# Temp_sensors_Input.net
KiCad netlist of a schematic drawn in Altium Designer
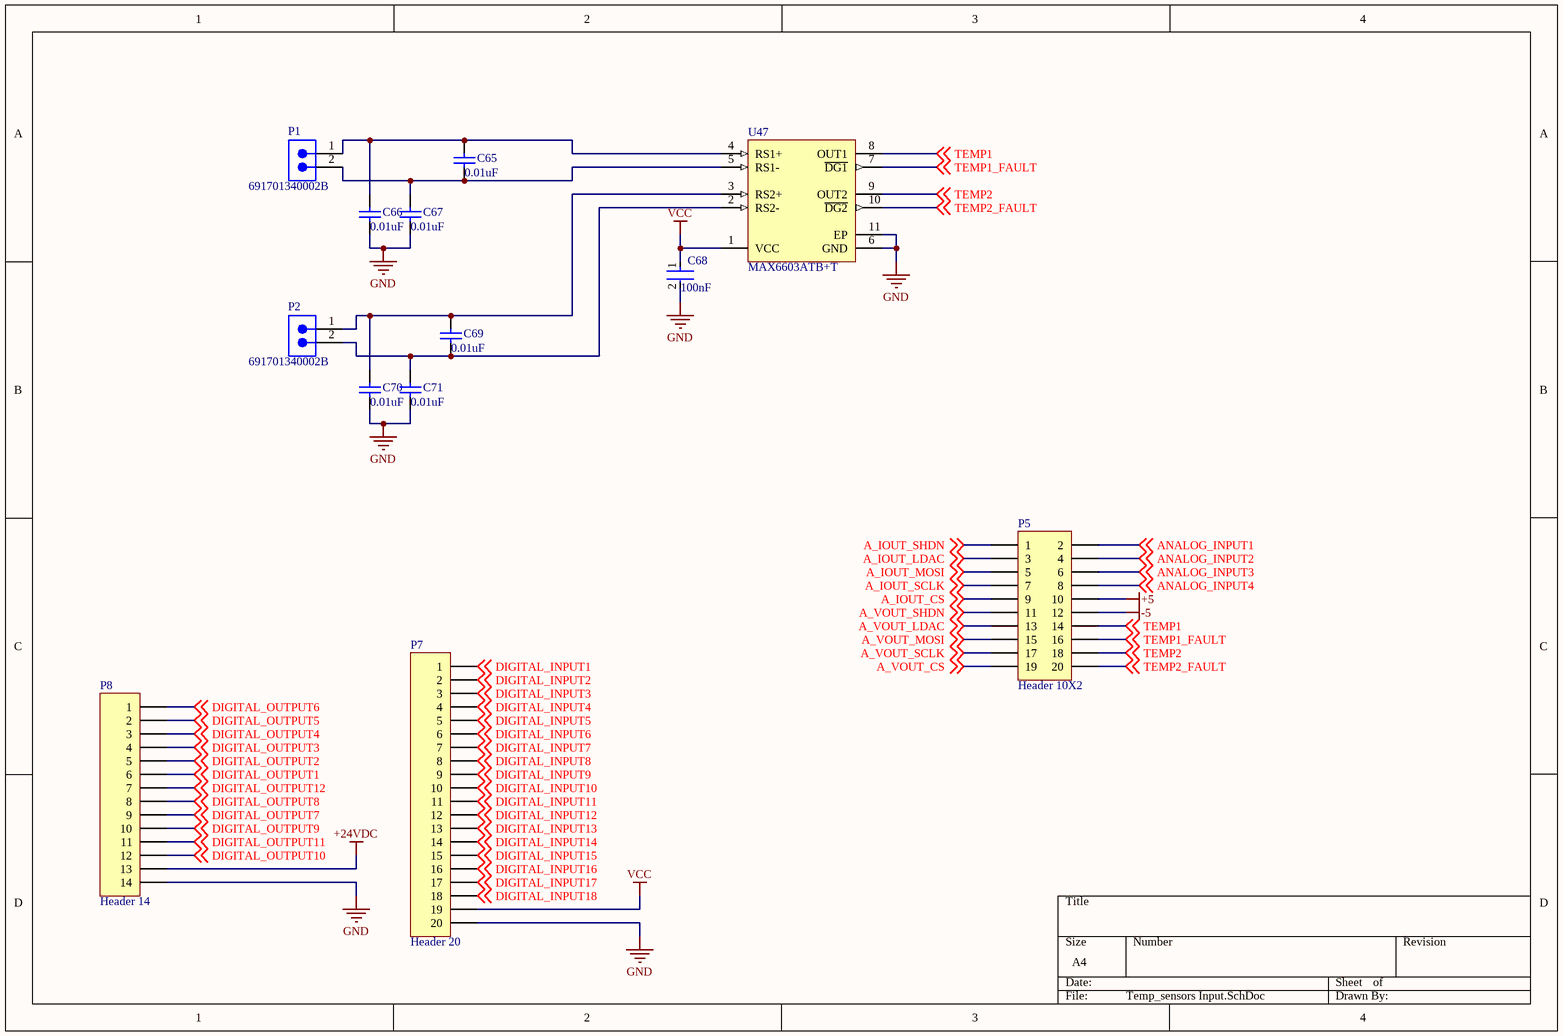
[diagram p0: Temp_sensors Input.SchDoc]

(export (version "E")
  (design (tool "Eeschema 10.0.6"))
  (components
    (comp (ref "C65")
      (value "0.01uF")
      (footprint "CAPC1608X92X38ML15T08")
      (fields (field (name "MANUFACTURER") "Vitramon") (field (name "PART NUMBER") "VJ0603Y103KXAAP"))
      (libsource (lib "Altium Content Vault") (part "CAP"))
    )
    (comp (ref "C66")
      (value "0.01uF")
      (footprint "CAPC1608X92X38ML15T08")
      (fields (field (name "MANUFACTURER") "Vitramon") (field (name "PART NUMBER") "VJ0603Y103KXAAP"))
      (libsource (lib "Altium Content Vault") (part "CAP"))
    )
    (comp (ref "C67")
      (value "0.01uF")
      (footprint "CAPC1608X92X38ML15T08")
      (fields (field (name "MANUFACTURER") "Vitramon") (field (name "PART NUMBER") "VJ0603Y103KXAAP"))
      (libsource (lib "Altium Content Vault") (part "CAP"))
    )
    (comp (ref "C68")
      (value "08051C104K4T2A")
      (footprint "FP-0805-L_2_01_0_2-W_1_25-IPC_B")
      (description "Automotive Ceramic Capacitor, 0805, 100nF, 10%, X7R, 15%, 100V")
      (fields
        (field (name "TOLERANCE") "10%")
        (field (name "CAPACITANCE") "100nF")
        (field (name "VOLTAGE") "100V")
      )
      (libsource (lib "Altium Content Vault") (part "b4654b650e69147ec39a6b967a45e02"))
    )
    (comp (ref "C69")
      (value "0.01uF")
      (footprint "CAPC1608X92X38ML15T08")
      (fields (field (name "MANUFACTURER") "Vitramon") (field (name "PART NUMBER") "VJ0603Y103KXAAP"))
      (libsource (lib "Altium Content Vault") (part "CAP"))
    )
    (comp (ref "C70")
      (value "0.01uF")
      (footprint "CAPC1608X92X38ML15T08")
      (fields (field (name "MANUFACTURER") "Vitramon") (field (name "PART NUMBER") "VJ0603Y103KXAAP"))
      (libsource (lib "Altium Content Vault") (part "CAP"))
    )
    (comp (ref "C71")
      (value "0.01uF")
      (footprint "CAPC1608X92X38ML15T08")
      (fields (field (name "MANUFACTURER") "Vitramon") (field (name "PART NUMBER") "VJ0603Y103KXAAP"))
      (libsource (lib "Altium Content Vault") (part "CAP"))
    )
    (comp (ref "P1")
      (value "691701340002B")
      (footprint "691701340002B")
      (libsource (lib "Altium Content Vault") (part "TBL - 1R - 02P - Male"))
    )
    (comp (ref "P2")
      (value "691701340002B")
      (footprint "691701340002B")
      (libsource (lib "Altium Content Vault") (part "TBL - 1R - 02P - Male"))
    )
    (comp (ref "P5")
      (value "Header 10X2")
      (footprint "HDR2X10")
      (description "Header, 10-Pin, Dual row")
      (fields (field (name "PUBLISHER") "Altium Limited"))
      (libsource (lib "Miscellaneous Connectors") (part "Header 10X2"))
    )
    (comp (ref "P7")
      (value "Header 20")
      (footprint "HDR1X20")
      (description "Header, 20-Pin")
      (fields (field (name "PUBLISHER") "Altium Limited"))
      (libsource (lib "Miscellaneous Connectors") (part "Header 20"))
    )
    (comp (ref "P8")
      (value "Header 14")
      (footprint "HDR1X14")
      (description "Header, 14-Pin")
      (fields (field (name "PUBLISHER") "Altium Limited"))
      (libsource (lib "Miscellaneous Connectors") (part "Header 14"))
    )
    (comp (ref "U47")
      (value "MAX6603ATB+T")
      (footprint "MAXM-T1033+1_V")
      (fields (field (name "GENERIC PART NUMBER") "MAX6603"))
      (libsource (lib "Altium Content Vault") (part "MAX6603-T1033"))
    )
  )
  (nets
    (net (code "1") (name "+5") (class "Default")
      (node (ref "P5") (pin "10") (pinfunction "10_10") (pintype "passive"))
    )
    (net (code "2") (name "+24VDC") (class "Default")
      (node (ref "P8") (pin "13") (pinfunction "13_13") (pintype "passive"))
    )
    (net (code "3") (name "-5") (class "Default")
      (node (ref "P5") (pin "12") (pinfunction "12_12") (pintype "passive"))
    )
    (net (code "4") (name "ANALOG_INPUT1") (class "Default")
      (node (ref "P5") (pin "2") (pinfunction "2_2") (pintype "passive"))
    )
    (net (code "5") (name "ANALOG_INPUT2") (class "Default")
      (node (ref "P5") (pin "4") (pinfunction "4_4") (pintype "passive"))
    )
    (net (code "6") (name "ANALOG_INPUT3") (class "Default")
      (node (ref "P5") (pin "6") (pinfunction "6_6") (pintype "passive"))
    )
    (net (code "7") (name "ANALOG_INPUT4") (class "Default")
      (node (ref "P5") (pin "8") (pinfunction "8_8") (pintype "passive"))
    )
    (net (code "8") (name "A_IOUT_CS") (class "Default")
      (node (ref "P5") (pin "9") (pinfunction "9_9") (pintype "passive"))
    )
    (net (code "9") (name "A_IOUT_LDAC") (class "Default")
      (node (ref "P5") (pin "3") (pinfunction "3_3") (pintype "passive"))
    )
    (net (code "10") (name "A_IOUT_MOSI") (class "Default")
      (node (ref "P5") (pin "5") (pinfunction "5_5") (pintype "passive"))
    )
    (net (code "11") (name "A_IOUT_SCLK") (class "Default")
      (node (ref "P5") (pin "7") (pinfunction "7_7") (pintype "passive"))
    )
    (net (code "12") (name "A_IOUT_SHDN") (class "Default")
      (node (ref "P5") (pin "1") (pinfunction "1_1") (pintype "passive"))
    )
    (net (code "13") (name "A_VOUT_CS") (class "Default")
      (node (ref "P5") (pin "19") (pinfunction "19_19") (pintype "passive"))
    )
    (net (code "14") (name "A_VOUT_LDAC") (class "Default")
      (node (ref "P5") (pin "13") (pinfunction "13_13") (pintype "passive"))
    )
    (net (code "15") (name "A_VOUT_MOSI") (class "Default")
      (node (ref "P5") (pin "15") (pinfunction "15_15") (pintype "passive"))
    )
    (net (code "16") (name "A_VOUT_SCLK") (class "Default")
      (node (ref "P5") (pin "17") (pinfunction "17_17") (pintype "passive"))
    )
    (net (code "17") (name "A_VOUT_SHDN") (class "Default")
      (node (ref "P5") (pin "11") (pinfunction "11_11") (pintype "passive"))
    )
    (net (code "18") (name "DIGITAL_INPUT1") (class "Default")
      (node (ref "P7") (pin "1") (pinfunction "1_1") (pintype "passive"))
    )
    (net (code "19") (name "DIGITAL_INPUT2") (class "Default")
      (node (ref "P7") (pin "2") (pinfunction "2_2") (pintype "passive"))
    )
    (net (code "20") (name "DIGITAL_INPUT3") (class "Default")
      (node (ref "P7") (pin "3") (pinfunction "3_3") (pintype "passive"))
    )
    (net (code "21") (name "DIGITAL_INPUT4") (class "Default")
      (node (ref "P7") (pin "4") (pinfunction "4_4") (pintype "passive"))
    )
    (net (code "22") (name "DIGITAL_INPUT5") (class "Default")
      (node (ref "P7") (pin "5") (pinfunction "5_5") (pintype "passive"))
    )
    (net (code "23") (name "DIGITAL_INPUT6") (class "Default")
      (node (ref "P7") (pin "6") (pinfunction "6_6") (pintype "passive"))
    )
    (net (code "24") (name "DIGITAL_INPUT7") (class "Default")
      (node (ref "P7") (pin "7") (pinfunction "7_7") (pintype "passive"))
    )
    (net (code "25") (name "DIGITAL_INPUT8") (class "Default")
      (node (ref "P7") (pin "8") (pinfunction "8_8") (pintype "passive"))
    )
    (net (code "26") (name "DIGITAL_INPUT9") (class "Default")
      (node (ref "P7") (pin "9") (pinfunction "9_9") (pintype "passive"))
    )
    (net (code "27") (name "DIGITAL_INPUT10") (class "Default")
      (node (ref "P7") (pin "10") (pinfunction "10_10") (pintype "passive"))
    )
    (net (code "28") (name "DIGITAL_INPUT11") (class "Default")
      (node (ref "P7") (pin "11") (pinfunction "11_11") (pintype "passive"))
    )
    (net (code "29") (name "DIGITAL_INPUT12") (class "Default")
      (node (ref "P7") (pin "12") (pinfunction "12_12") (pintype "passive"))
    )
    (net (code "30") (name "DIGITAL_INPUT13") (class "Default")
      (node (ref "P7") (pin "13") (pinfunction "13_13") (pintype "passive"))
    )
    (net (code "31") (name "DIGITAL_INPUT14") (class "Default")
      (node (ref "P7") (pin "14") (pinfunction "14_14") (pintype "passive"))
    )
    (net (code "32") (name "DIGITAL_INPUT15") (class "Default")
      (node (ref "P7") (pin "15") (pinfunction "15_15") (pintype "passive"))
    )
    (net (code "33") (name "DIGITAL_INPUT16") (class "Default")
      (node (ref "P7") (pin "16") (pinfunction "16_16") (pintype "passive"))
    )
    (net (code "34") (name "DIGITAL_INPUT17") (class "Default")
      (node (ref "P7") (pin "17") (pinfunction "17_17") (pintype "passive"))
    )
    (net (code "35") (name "DIGITAL_INPUT18") (class "Default")
      (node (ref "P7") (pin "18") (pinfunction "18_18") (pintype "passive"))
    )
    (net (code "36") (name "DIGITAL_OUTPUT1") (class "Default")
      (node (ref "P8") (pin "6") (pinfunction "6_6") (pintype "passive"))
    )
    (net (code "37") (name "DIGITAL_OUTPUT2") (class "Default")
      (node (ref "P8") (pin "5") (pinfunction "5_5") (pintype "passive"))
    )
    (net (code "38") (name "DIGITAL_OUTPUT3") (class "Default")
      (node (ref "P8") (pin "4") (pinfunction "4_4") (pintype "passive"))
    )
    (net (code "39") (name "DIGITAL_OUTPUT4") (class "Default")
      (node (ref "P8") (pin "3") (pinfunction "3_3") (pintype "passive"))
    )
    (net (code "40") (name "DIGITAL_OUTPUT5") (class "Default")
      (node (ref "P8") (pin "2") (pinfunction "2_2") (pintype "passive"))
    )
    (net (code "41") (name "DIGITAL_OUTPUT6") (class "Default")
      (node (ref "P8") (pin "1") (pinfunction "1_1") (pintype "passive"))
    )
    (net (code "42") (name "DIGITAL_OUTPUT7") (class "Default")
      (node (ref "P8") (pin "9") (pinfunction "9_9") (pintype "passive"))
    )
    (net (code "43") (name "DIGITAL_OUTPUT8") (class "Default")
      (node (ref "P8") (pin "8") (pinfunction "8_8") (pintype "passive"))
    )
    (net (code "44") (name "DIGITAL_OUTPUT9") (class "Default")
      (node (ref "P8") (pin "10") (pinfunction "10_10") (pintype "passive"))
    )
    (net (code "45") (name "DIGITAL_OUTPUT10") (class "Default")
      (node (ref "P8") (pin "12") (pinfunction "12_12") (pintype "passive"))
    )
    (net (code "46") (name "DIGITAL_OUTPUT11") (class "Default")
      (node (ref "P8") (pin "11") (pinfunction "11_11") (pintype "passive"))
    )
    (net (code "47") (name "DIGITAL_OUTPUT12") (class "Default")
      (node (ref "P8") (pin "7") (pinfunction "7_7") (pintype "passive"))
    )
    (net (code "48") (name "GND") (class "Default")
      (node (ref "C66") (pin "1") (pinfunction "1_1") (pintype "passive"))
      (node (ref "C67") (pin "1") (pinfunction "1_1") (pintype "passive"))
      (node (ref "C68") (pin "2") (pinfunction "2_2") (pintype "passive"))
      (node (ref "C70") (pin "1") (pinfunction "1_1") (pintype "passive"))
      (node (ref "C71") (pin "1") (pinfunction "1_1") (pintype "passive"))
      (node (ref "P7") (pin "20") (pinfunction "20_20") (pintype "passive"))
      (node (ref "P8") (pin "14") (pinfunction "14_14") (pintype "passive"))
      (node (ref "U47") (pin "11") (pinfunction "EP_11") (pintype "power_in"))
      (node (ref "U47") (pin "6") (pinfunction "GND_6") (pintype "power_in"))
    )
    (net (code "49") (name "Net-(U47-RS1+)") (class "Default")
      (node (ref "C65") (pin "2") (pinfunction "2_2") (pintype "passive"))
      (node (ref "C66") (pin "2") (pinfunction "2_2") (pintype "passive"))
      (node (ref "P1") (pin "1") (pinfunction "1_1") (pintype "passive"))
      (node (ref "U47") (pin "4") (pinfunction "RS1+_4") (pintype "input"))
    )
    (net (code "50") (name "Net-(U47-RS1-)") (class "Default")
      (node (ref "C65") (pin "1") (pinfunction "1_1") (pintype "passive"))
      (node (ref "C67") (pin "2") (pinfunction "2_2") (pintype "passive"))
      (node (ref "P1") (pin "2") (pinfunction "2_2") (pintype "passive"))
      (node (ref "U47") (pin "5") (pinfunction "RS1-_5") (pintype "input"))
    )
    (net (code "51") (name "Net-(U47-RS2+)") (class "Default")
      (node (ref "C69") (pin "2") (pinfunction "2_2") (pintype "passive"))
      (node (ref "C70") (pin "2") (pinfunction "2_2") (pintype "passive"))
      (node (ref "P2") (pin "1") (pinfunction "1_1") (pintype "passive"))
      (node (ref "U47") (pin "3") (pinfunction "RS2+_3") (pintype "input"))
    )
    (net (code "52") (name "Net-(U47-RS2-)") (class "Default")
      (node (ref "C69") (pin "1") (pinfunction "1_1") (pintype "passive"))
      (node (ref "C71") (pin "2") (pinfunction "2_2") (pintype "passive"))
      (node (ref "P2") (pin "2") (pinfunction "2_2") (pintype "passive"))
      (node (ref "U47") (pin "2") (pinfunction "RS2-_2") (pintype "input"))
    )
    (net (code "53") (name "TEMP1") (class "Default")
      (node (ref "P5") (pin "14") (pinfunction "14_14") (pintype "passive"))
      (node (ref "U47") (pin "8") (pinfunction "OUT1_8") (pintype "tri_state"))
    )
    (net (code "54") (name "TEMP1_FAULT") (class "Default")
      (node (ref "P5") (pin "16") (pinfunction "16_16") (pintype "passive"))
      (node (ref "U47") (pin "7") (pinfunction "~{DG1}_7") (pintype "output"))
    )
    (net (code "55") (name "TEMP2") (class "Default")
      (node (ref "P5") (pin "18") (pinfunction "18_18") (pintype "passive"))
      (node (ref "U47") (pin "9") (pinfunction "OUT2_9") (pintype "tri_state"))
    )
    (net (code "56") (name "TEMP2_FAULT") (class "Default")
      (node (ref "P5") (pin "20") (pinfunction "20_20") (pintype "passive"))
      (node (ref "U47") (pin "10") (pinfunction "~{DG2}_10") (pintype "output"))
    )
    (net (code "57") (name "VCC") (class "Default")
      (node (ref "C68") (pin "1") (pinfunction "1_1") (pintype "passive"))
      (node (ref "P7") (pin "19") (pinfunction "19_19") (pintype "passive"))
      (node (ref "U47") (pin "1") (pinfunction "VCC_1") (pintype "power_in"))
    )
  )
)
